# bottom.net
KiCad netlist of a schematic drawn in EAGLE
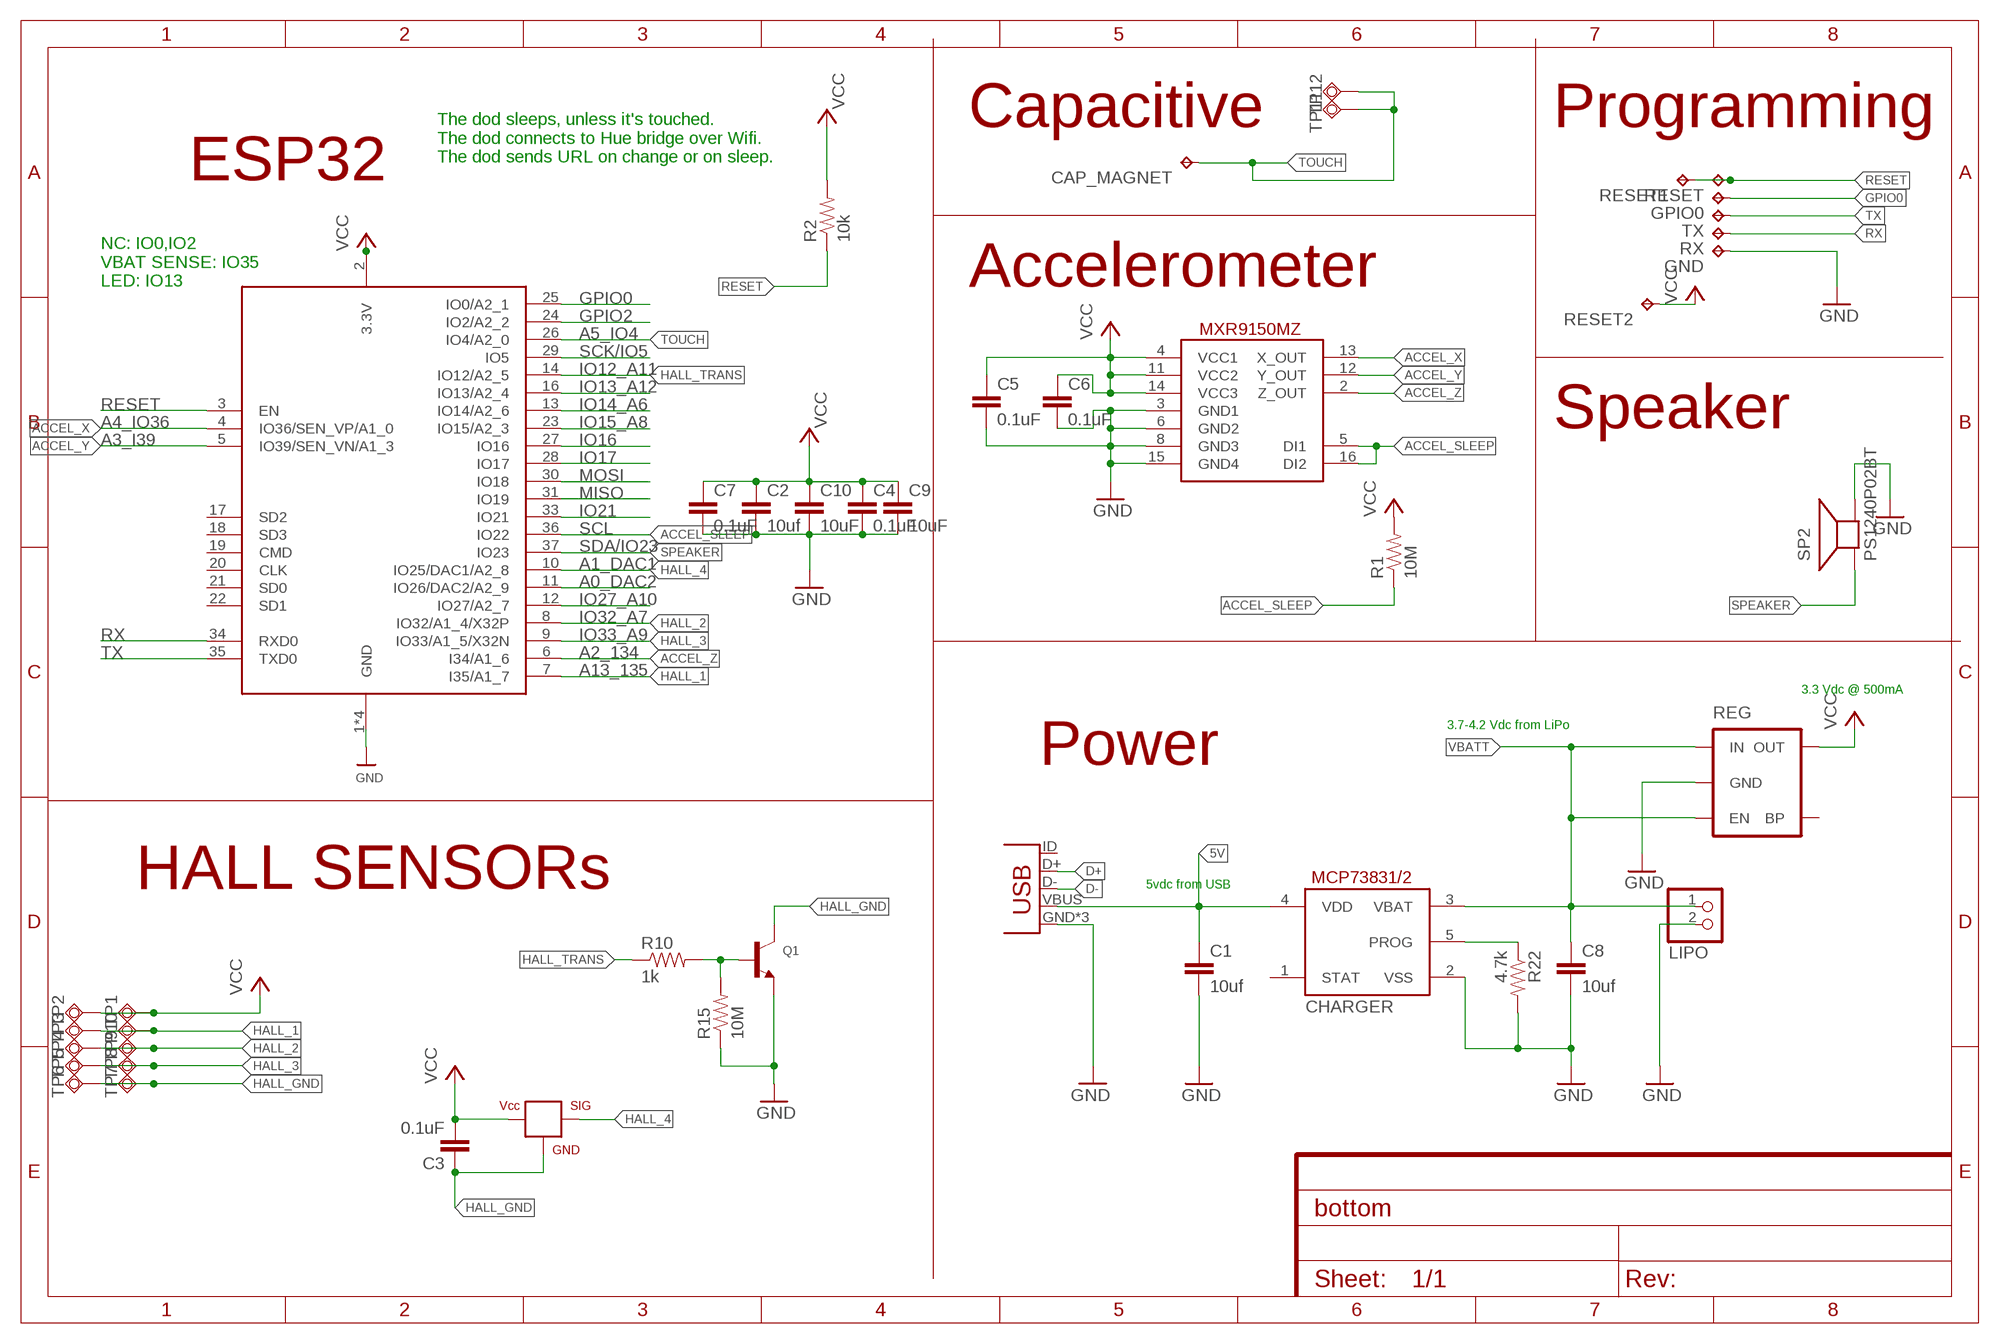
[diagram p0: schematic, sheet 1]

(export (version "E")
  (design (tool "Eeschema 10.0.6"))
  (components
    (comp (ref "C1")
      (value "10uf")
      (footprint "eagle-import:0603-CAP")
      (libsource (lib "eagle-import") (part "SparkFun-Capacitors_CAP0603-CAP"))
    )
    (comp (ref "C2")
      (value "10uf")
      (footprint "eagle-import:0402-CAP")
      (libsource (lib "eagle-import") (part "CAP0402-CAP"))
    )
    (comp (ref "C3")
      (value "0.1uF")
      (footprint "eagle-import:0603-CAP")
      (libsource (lib "eagle-import") (part "CAP0603-CAP"))
    )
    (comp (ref "C4")
      (value "0.1uF")
      (footprint "eagle-import:0402-CAP")
      (libsource (lib "eagle-import") (part "CAP0402-CAP"))
    )
    (comp (ref "C5")
      (value "0.1uF")
      (footprint "eagle-import:0402-CAP")
      (libsource (lib "eagle-import") (part "CAP0402-CAP"))
    )
    (comp (ref "C6")
      (value "0.1uF")
      (footprint "eagle-import:0402-CAP")
      (libsource (lib "eagle-import") (part "CAP0402-CAP"))
    )
    (comp (ref "C7")
      (value "0.1uF")
      (footprint "eagle-import:0402-CAP")
      (libsource (lib "eagle-import") (part "CAP0402-CAP"))
    )
    (comp (ref "C8")
      (value "10uf")
      (footprint "eagle-import:0603-CAP")
      (libsource (lib "eagle-import") (part "SparkFun-Capacitors_CAP0603-CAP"))
    )
    (comp (ref "C9")
      (value "10uF")
      (footprint "eagle-import:0402-CAP")
      (libsource (lib "eagle-import") (part "CAP0402-CAP"))
    )
    (comp (ref "C10")
      (value "10uF")
      (footprint "eagle-import:0402-CAP")
      (libsource (lib "eagle-import") (part "CAP0402-CAP"))
    )
    (comp (ref "CAP_MAGNET")
      (value "TPTP10R")
      (footprint "eagle-import:TP10R")
      (libsource (lib "eagle-import") (part "TPTP10R"))
    )
    (comp (ref "CHARGER")
      (value "MCP73831/OT")
      (footprint "eagle-import:SOT23-5L")
      (libsource (lib "eagle-import") (part "MCP73831/OT"))
    )
    (comp (ref "GND")
      (value "TPTP13SQ")
      (footprint "eagle-import:TP13SQ")
      (libsource (lib "eagle-import") (part "TPTP13SQ"))
    )
    (comp (ref "GPIO0")
      (value "TPTP13R")
      (footprint "eagle-import:TP13R")
      (libsource (lib "eagle-import") (part "TPTP13R"))
    )
    (comp (ref "HALL")
      (value "A1304")
      (footprint "eagle-import:SOT23-3")
      (libsource (lib "eagle-import") (part "HALLEFFECT-A1326"))
    )
    (comp (ref "JP1")
      (value "USB-MICROB")
      (footprint "eagle-import:USB-MICROB")
      (libsource (lib "eagle-import") (part "USB-MICROB"))
    )
    (comp (ref "LIPO")
      (value "JST_2PIN-THM")
      (footprint "eagle-import:JST-PH-2-THM")
      (libsource (lib "eagle-import") (part "JST_2PIN-THM"))
    )
    (comp (ref "Q1")
      (value "TRANSISTOR_NPN")
      (footprint "eagle-import:SOT-23-R")
      (libsource (lib "eagle-import") (part "TRANSISTOR_NPN"))
    )
    (comp (ref "R1")
      (value "10M")
      (footprint "eagle-import:0402-RES")
      (libsource (lib "eagle-import") (part "RESISTOR0402-RES"))
    )
    (comp (ref "R2")
      (value "10k")
      (footprint "eagle-import:0402-RES")
      (libsource (lib "eagle-import") (part "RESISTOR0402-RES"))
    )
    (comp (ref "R10")
      (value "1k")
      (footprint "eagle-import:0402-RES")
      (libsource (lib "eagle-import") (part "RESISTOR0402-RES"))
    )
    (comp (ref "R15")
      (value "10M")
      (footprint "eagle-import:0402-RES")
      (libsource (lib "eagle-import") (part "RESISTOR0402-RES"))
    )
    (comp (ref "R22")
      (value "4.7k")
      (footprint "eagle-import:0402-RES")
      (libsource (lib "eagle-import") (part "RESISTOR0402-RES"))
    )
    (comp (ref "REG")
      (value "MIC52053.3V")
      (footprint "eagle-import:SOT23-5")
      (libsource (lib "eagle-import") (part "MIC52053.3V"))
    )
    (comp (ref "RESET")
      (value "TPTP13R")
      (footprint "eagle-import:TP13R")
      (libsource (lib "eagle-import") (part "TPTP13R"))
    )
    (comp (ref "RESET1")
      (value "TPTP13R")
      (footprint "eagle-import:TP13R")
      (libsource (lib "eagle-import") (part "TPTP13R"))
    )
    (comp (ref "RESET2")
      (value "TPTP13R")
      (footprint "eagle-import:TP13R")
      (libsource (lib "eagle-import") (part "TPTP13R"))
    )
    (comp (ref "RX")
      (value "TPTP13R")
      (footprint "eagle-import:TP13R")
      (libsource (lib "eagle-import") (part "TPTP13R"))
    )
    (comp (ref "SP2")
      (value "PS1240P02BT")
      (footprint "eagle-import:PS12")
      (libsource (lib "eagle-import") (part "SPEAKER/PS12"))
    )
    (comp (ref "TP1")
      (value "TPSQTP10SQ")
      (footprint "eagle-import:TP10SQ")
      (libsource (lib "eagle-import") (part "TPSQTP10SQ"))
    )
    (comp (ref "TP2")
      (value "TPSQTP10SQ")
      (footprint "eagle-import:TP10SQ")
      (libsource (lib "eagle-import") (part "TPSQTP10SQ"))
    )
    (comp (ref "TP3")
      (value "TPSQTP10SQ")
      (footprint "eagle-import:TP10SQ")
      (libsource (lib "eagle-import") (part "TPSQTP10SQ"))
    )
    (comp (ref "TP4")
      (value "TPSQTP10SQ")
      (footprint "eagle-import:TP10SQ")
      (libsource (lib "eagle-import") (part "TPSQTP10SQ"))
    )
    (comp (ref "TP5")
      (value "TPSQTP10SQ")
      (footprint "eagle-import:TP10SQ")
      (libsource (lib "eagle-import") (part "TPSQTP10SQ"))
    )
    (comp (ref "TP6")
      (value "TPSQTP10SQ")
      (footprint "eagle-import:TP10SQ")
      (libsource (lib "eagle-import") (part "TPSQTP10SQ"))
    )
    (comp (ref "TP7")
      (value "TPSQTP10SQ")
      (footprint "eagle-import:TP10SQ")
      (libsource (lib "eagle-import") (part "TPSQTP10SQ"))
    )
    (comp (ref "TP8")
      (value "TPSQTP10SQ")
      (footprint "eagle-import:TP10SQ")
      (libsource (lib "eagle-import") (part "TPSQTP10SQ"))
    )
    (comp (ref "TP9")
      (value "TPSQTP10SQ")
      (footprint "eagle-import:TP10SQ")
      (libsource (lib "eagle-import") (part "TPSQTP10SQ"))
    )
    (comp (ref "TP10")
      (value "TPSQTP10SQ")
      (footprint "eagle-import:TP10SQ")
      (libsource (lib "eagle-import") (part "TPSQTP10SQ"))
    )
    (comp (ref "TP11")
      (value "TPSQTP10SQ")
      (footprint "eagle-import:TP10SQ")
      (libsource (lib "eagle-import") (part "TPSQTP10SQ"))
    )
    (comp (ref "TP12")
      (value "TPSQTP10SQ")
      (footprint "eagle-import:TP10SQ")
      (libsource (lib "eagle-import") (part "TPSQTP10SQ"))
    )
    (comp (ref "TX")
      (value "TPTP13R")
      (footprint "eagle-import:TP13R")
      (libsource (lib "eagle-import") (part "TPTP13R"))
    )
    (comp (ref "U$1")
      (value "ACCELEROMETER_MXR9150MZ")
      (footprint "eagle-import:MXR9150MZ")
      (libsource (lib "eagle-import") (part "ACCELEROMETER_MXR9150MZ"))
    )
    (comp (ref "X2")
      (value "ESP32_WROOM32_SKINNY")
      (footprint "eagle-import:WROOM32_SKINNY")
      (libsource (lib "eagle-import") (part "ESP32_WROOM32_SKINNY"))
    )
  )
  (nets
    (net (code "1") (name "/A0_DAC2") (class "Default")
      (node (ref "X2") (pin "11") (pinfunction "IO26/DAC2/A2_9_11") (pintype "bidirectional"))
    )
    (net (code "2") (name "/GPIO2") (class "Default")
      (node (ref "X2") (pin "24") (pinfunction "IO2/A2_2_24") (pintype "bidirectional"))
    )
    (net (code "3") (name "/IO16") (class "Default")
      (node (ref "X2") (pin "27") (pinfunction "IO16_27") (pintype "bidirectional"))
    )
    (net (code "4") (name "/IO17") (class "Default")
      (node (ref "X2") (pin "28") (pinfunction "IO17_28") (pintype "bidirectional"))
    )
    (net (code "5") (name "/IO21") (class "Default")
      (node (ref "X2") (pin "33") (pinfunction "IO21_33") (pintype "bidirectional"))
    )
    (net (code "6") (name "/MISO") (class "Default")
      (node (ref "X2") (pin "31") (pinfunction "IO19_31") (pintype "bidirectional"))
    )
    (net (code "7") (name "/MOSI") (class "Default")
      (node (ref "X2") (pin "30") (pinfunction "IO18_30") (pintype "bidirectional"))
    )
    (net (code "8") (name "5V") (class "Default")
      (node (ref "C1") (pin "1") (pinfunction "1_1") (pintype "passive"))
      (node (ref "CHARGER") (pin "4") (pinfunction "VDD_4") (pintype "power_in"))
      (node (ref "JP1") (pin "VBUS") (pinfunction "VBUS_VBUS") (pintype "bidirectional"))
    )
    (net (code "9") (name "ACCEL_SLEEP") (class "Default")
      (node (ref "R1") (pin "1") (pinfunction "1_1") (pintype "passive"))
      (node (ref "U$1") (pin "16") (pinfunction "DI2_16") (pintype "bidirectional"))
      (node (ref "U$1") (pin "5") (pinfunction "DI1_5") (pintype "bidirectional"))
      (node (ref "X2") (pin "36") (pinfunction "IO22_36") (pintype "bidirectional"))
    )
    (net (code "10") (name "ACCEL_X") (class "Default")
      (node (ref "U$1") (pin "13") (pinfunction "X_OUT_13") (pintype "bidirectional"))
      (node (ref "X2") (pin "4") (pinfunction "IO36/SEN_VP/A1_0_4") (pintype "passive"))
    )
    (net (code "11") (name "ACCEL_Y") (class "Default")
      (node (ref "U$1") (pin "12") (pinfunction "Y_OUT_12") (pintype "bidirectional"))
      (node (ref "X2") (pin "5") (pinfunction "IO39/SEN_VN/A1_3_5") (pintype "passive"))
    )
    (net (code "12") (name "ACCEL_Z") (class "Default")
      (node (ref "U$1") (pin "2") (pinfunction "Z_OUT_2") (pintype "bidirectional"))
      (node (ref "X2") (pin "6") (pinfunction "I34/A1_6_6") (pintype "bidirectional"))
    )
    (net (code "13") (name "D+") (class "Default")
      (node (ref "JP1") (pin "D+") (pinfunction "D+_D+") (pintype "bidirectional"))
    )
    (net (code "14") (name "D-") (class "Default")
      (node (ref "JP1") (pin "D-") (pinfunction "D-_D-") (pintype "bidirectional"))
    )
    (net (code "15") (name "GND") (class "Default")
      (node (ref "C1") (pin "2") (pinfunction "2_2") (pintype "passive"))
      (node (ref "C10") (pin "2") (pinfunction "2_2") (pintype "passive"))
      (node (ref "C2") (pin "2") (pinfunction "2_2") (pintype "passive"))
      (node (ref "C4") (pin "2") (pinfunction "2_2") (pintype "passive"))
      (node (ref "C5") (pin "2") (pinfunction "2_2") (pintype "passive"))
      (node (ref "C6") (pin "2") (pinfunction "2_2") (pintype "passive"))
      (node (ref "C7") (pin "2") (pinfunction "2_2") (pintype "passive"))
      (node (ref "C8") (pin "2") (pinfunction "2_2") (pintype "passive"))
      (node (ref "C9") (pin "2") (pinfunction "2_2") (pintype "passive"))
      (node (ref "CHARGER") (pin "2") (pinfunction "VSS_2") (pintype "power_in"))
      (node (ref "GND") (pin "TP") (pinfunction "TP_TP") (pintype "input"))
      (node (ref "JP1") (pin "GND") (pinfunction "GND_GND") (pintype "bidirectional"))
      (node (ref "JP1") (pin "MT1") (pinfunction "GND_MT1") (pintype "bidirectional"))
      (node (ref "JP1") (pin "MT2") (pinfunction "GND_MT2") (pintype "bidirectional"))
      (node (ref "LIPO") (pin "2") (pinfunction "1_2") (pintype "passive"))
      (node (ref "Q1") (pin "3-EMITTER") (pinfunction "E_3-EMITTER") (pintype "passive"))
      (node (ref "R15") (pin "1") (pinfunction "1_1") (pintype "passive"))
      (node (ref "R22") (pin "2") (pinfunction "2_2") (pintype "passive"))
      (node (ref "REG") (pin "2") (pinfunction "GND_2") (pintype "input"))
      (node (ref "SP2") (pin "P$2") (pinfunction "-_P$2") (pintype "passive"))
      (node (ref "U$1") (pin "15") (pinfunction "GND4_15") (pintype "bidirectional"))
      (node (ref "U$1") (pin "3") (pinfunction "GND1_3") (pintype "bidirectional"))
      (node (ref "U$1") (pin "6") (pinfunction "GND2_6") (pintype "bidirectional"))
      (node (ref "U$1") (pin "8") (pinfunction "GND3_8") (pintype "bidirectional"))
      (node (ref "X2") (pin "1") (pinfunction "GND_1") (pintype "passive"))
      (node (ref "X2") (pin "15") (pinfunction "GND_15") (pintype "passive"))
      (node (ref "X2") (pin "38") (pinfunction "GND_38") (pintype "passive"))
      (node (ref "X2") (pin "P$1") (pinfunction "GND_P$1") (pintype "passive"))
    )
    (net (code "16") (name "GPIO0") (class "Default")
      (node (ref "GPIO0") (pin "TP") (pinfunction "TP_TP") (pintype "input"))
      (node (ref "X2") (pin "25") (pinfunction "IO0/A2_1_25") (pintype "bidirectional"))
    )
    (net (code "17") (name "HALL_1") (class "Default")
      (node (ref "TP10") (pin "TP") (pinfunction "TP_TP") (pintype "input"))
      (node (ref "TP3") (pin "TP") (pinfunction "TP_TP") (pintype "input"))
      (node (ref "X2") (pin "7") (pinfunction "I35/A1_7_7") (pintype "bidirectional"))
    )
    (net (code "18") (name "HALL_2") (class "Default")
      (node (ref "TP4") (pin "TP") (pinfunction "TP_TP") (pintype "input"))
      (node (ref "TP9") (pin "TP") (pinfunction "TP_TP") (pintype "input"))
      (node (ref "X2") (pin "8") (pinfunction "IO32/A1_4/X32P_8") (pintype "bidirectional"))
    )
    (net (code "19") (name "HALL_3") (class "Default")
      (node (ref "TP5") (pin "TP") (pinfunction "TP_TP") (pintype "input"))
      (node (ref "TP8") (pin "TP") (pinfunction "TP_TP") (pintype "input"))
      (node (ref "X2") (pin "9") (pinfunction "IO33/A1_5/X32N_9") (pintype "bidirectional"))
    )
    (net (code "20") (name "HALL_4") (class "Default")
      (node (ref "HALL") (pin "2") (pinfunction "SIG_2") (pintype "bidirectional"))
      (node (ref "X2") (pin "10") (pinfunction "IO25/DAC1/A2_8_10") (pintype "bidirectional"))
    )
    (net (code "21") (name "HALL_GND") (class "Default")
      (node (ref "C3") (pin "1") (pinfunction "1_1") (pintype "passive"))
      (node (ref "HALL") (pin "3") (pinfunction "GND_3") (pintype "bidirectional"))
      (node (ref "Q1") (pin "2-COLLECTOR") (pinfunction "C_2-COLLECTOR") (pintype "passive"))
      (node (ref "TP6") (pin "TP") (pinfunction "TP_TP") (pintype "input"))
      (node (ref "TP7") (pin "TP") (pinfunction "TP_TP") (pintype "input"))
    )
    (net (code "22") (name "HALL_TRANS") (class "Default")
      (node (ref "R10") (pin "1") (pinfunction "1_1") (pintype "passive"))
      (node (ref "X2") (pin "14") (pinfunction "IO12/A2_5_14") (pintype "bidirectional"))
    )
    (net (code "23") (name "Net-(CHARGER-PROG)") (class "Default")
      (node (ref "CHARGER") (pin "5") (pinfunction "PROG_5") (pintype "input"))
      (node (ref "R22") (pin "1") (pinfunction "1_1") (pintype "passive"))
    )
    (net (code "24") (name "Net-(Q1-B)") (class "Default")
      (node (ref "Q1") (pin "1-BASE") (pinfunction "B_1-BASE") (pintype "passive"))
      (node (ref "R10") (pin "2") (pinfunction "2_2") (pintype "passive"))
      (node (ref "R15") (pin "2") (pinfunction "2_2") (pintype "passive"))
    )
    (net (code "25") (name "RESET") (class "Default")
      (node (ref "R2") (pin "1") (pinfunction "1_1") (pintype "passive"))
      (node (ref "RESET") (pin "TP") (pinfunction "TP_TP") (pintype "input"))
      (node (ref "RESET1") (pin "TP") (pinfunction "TP_TP") (pintype "input"))
      (node (ref "X2") (pin "3") (pinfunction "EN_3") (pintype "input"))
    )
    (net (code "26") (name "RX") (class "Default")
      (node (ref "RX") (pin "TP") (pinfunction "TP_TP") (pintype "input"))
      (node (ref "X2") (pin "34") (pinfunction "RXD0_34") (pintype "input"))
    )
    (net (code "27") (name "SPEAKER") (class "Default")
      (node (ref "SP2") (pin "P$1") (pinfunction "+_P$1") (pintype "passive"))
      (node (ref "X2") (pin "37") (pinfunction "IO23_37") (pintype "bidirectional"))
    )
    (net (code "28") (name "TOUCH") (class "Default")
      (node (ref "CAP_MAGNET") (pin "TP") (pinfunction "TP_TP") (pintype "input"))
      (node (ref "TP11") (pin "TP") (pinfunction "TP_TP") (pintype "input"))
      (node (ref "TP12") (pin "TP") (pinfunction "TP_TP") (pintype "input"))
      (node (ref "X2") (pin "26") (pinfunction "IO4/A2_0_26") (pintype "bidirectional"))
    )
    (net (code "29") (name "TX") (class "Default")
      (node (ref "TX") (pin "TP") (pinfunction "TP_TP") (pintype "input"))
      (node (ref "X2") (pin "35") (pinfunction "TXD0_35") (pintype "output"))
    )
    (net (code "30") (name "VBATT") (class "Default")
      (node (ref "C8") (pin "1") (pinfunction "1_1") (pintype "passive"))
      (node (ref "CHARGER") (pin "3") (pinfunction "VBAT_3") (pintype "bidirectional"))
      (node (ref "LIPO") (pin "1") (pinfunction "2_1") (pintype "passive"))
      (node (ref "REG") (pin "1") (pinfunction "IN_1") (pintype "input"))
      (node (ref "REG") (pin "3") (pinfunction "EN_3") (pintype "input"))
    )
    (net (code "31") (name "VCC") (class "Default")
      (node (ref "C10") (pin "1") (pinfunction "1_1") (pintype "passive"))
      (node (ref "C2") (pin "1") (pinfunction "1_1") (pintype "passive"))
      (node (ref "C3") (pin "2") (pinfunction "2_2") (pintype "passive"))
      (node (ref "C4") (pin "1") (pinfunction "1_1") (pintype "passive"))
      (node (ref "C5") (pin "1") (pinfunction "1_1") (pintype "passive"))
      (node (ref "C6") (pin "1") (pinfunction "1_1") (pintype "passive"))
      (node (ref "C7") (pin "1") (pinfunction "1_1") (pintype "passive"))
      (node (ref "C9") (pin "1") (pinfunction "1_1") (pintype "passive"))
      (node (ref "HALL") (pin "1") (pinfunction "VCC_1") (pintype "bidirectional"))
      (node (ref "R1") (pin "2") (pinfunction "2_2") (pintype "passive"))
      (node (ref "R2") (pin "2") (pinfunction "2_2") (pintype "passive"))
      (node (ref "REG") (pin "5") (pinfunction "OUT_5") (pintype "passive"))
      (node (ref "RESET2") (pin "TP") (pinfunction "TP_TP") (pintype "input"))
      (node (ref "TP1") (pin "TP") (pinfunction "TP_TP") (pintype "input"))
      (node (ref "TP2") (pin "TP") (pinfunction "TP_TP") (pintype "input"))
      (node (ref "U$1") (pin "11") (pinfunction "VCC2_11") (pintype "bidirectional"))
      (node (ref "U$1") (pin "14") (pinfunction "VCC3_14") (pintype "bidirectional"))
      (node (ref "U$1") (pin "4") (pinfunction "VCC1_4") (pintype "bidirectional"))
      (node (ref "X2") (pin "2") (pinfunction "3.3V_2") (pintype "passive"))
    )
    (net (code "32") (name "unconnected-(CHARGER-STAT-Pad1)") (class "Default")
      (node (ref "CHARGER") (pin "1") (pinfunction "STAT_1") (pintype "output"))
    )
    (net (code "33") (name "unconnected-(JP1-SHIELD-PadID)") (class "Default")
      (node (ref "JP1") (pin "ID") (pinfunction "SHIELD_ID") (pintype "bidirectional"))
    )
    (net (code "34") (name "unconnected-(REG-BP-Pad4)") (class "Default")
      (node (ref "REG") (pin "4") (pinfunction "BP_4") (pintype "input"))
    )
    (net (code "35") (name "unconnected-(X2-CLK-Pad20)") (class "Default")
      (node (ref "X2") (pin "20") (pinfunction "CLK_20") (pintype "bidirectional"))
    )
    (net (code "36") (name "unconnected-(X2-CMD-Pad19)") (class "Default")
      (node (ref "X2") (pin "19") (pinfunction "CMD_19") (pintype "bidirectional"))
    )
    (net (code "37") (name "unconnected-(X2-IO5-Pad29)") (class "Default")
      (node (ref "X2") (pin "29") (pinfunction "IO5_29") (pintype "bidirectional"))
    )
    (net (code "38") (name "unconnected-(X2-IO13{slash}A2_4-Pad16)") (class "Default")
      (node (ref "X2") (pin "16") (pinfunction "IO13/A2_4_16") (pintype "bidirectional"))
    )
    (net (code "39") (name "unconnected-(X2-IO14{slash}A2_6-Pad13)") (class "Default")
      (node (ref "X2") (pin "13") (pinfunction "IO14/A2_6_13") (pintype "bidirectional"))
    )
    (net (code "40") (name "unconnected-(X2-IO15{slash}A2_3-Pad23)") (class "Default")
      (node (ref "X2") (pin "23") (pinfunction "IO15/A2_3_23") (pintype "bidirectional"))
    )
    (net (code "41") (name "unconnected-(X2-IO27{slash}A2_7-Pad12)") (class "Default")
      (node (ref "X2") (pin "12") (pinfunction "IO27/A2_7_12") (pintype "bidirectional"))
    )
    (net (code "42") (name "unconnected-(X2-SD0-Pad21)") (class "Default")
      (node (ref "X2") (pin "21") (pinfunction "SD0_21") (pintype "bidirectional"))
    )
    (net (code "43") (name "unconnected-(X2-SD1-Pad22)") (class "Default")
      (node (ref "X2") (pin "22") (pinfunction "SD1_22") (pintype "bidirectional"))
    )
    (net (code "44") (name "unconnected-(X2-SD2-Pad17)") (class "Default")
      (node (ref "X2") (pin "17") (pinfunction "SD2_17") (pintype "bidirectional"))
    )
    (net (code "45") (name "unconnected-(X2-SD3-Pad18)") (class "Default")
      (node (ref "X2") (pin "18") (pinfunction "SD3_18") (pintype "bidirectional"))
    )
  )
)
